# Cosmic.net
KiCad netlist of a schematic drawn in Altium Designer
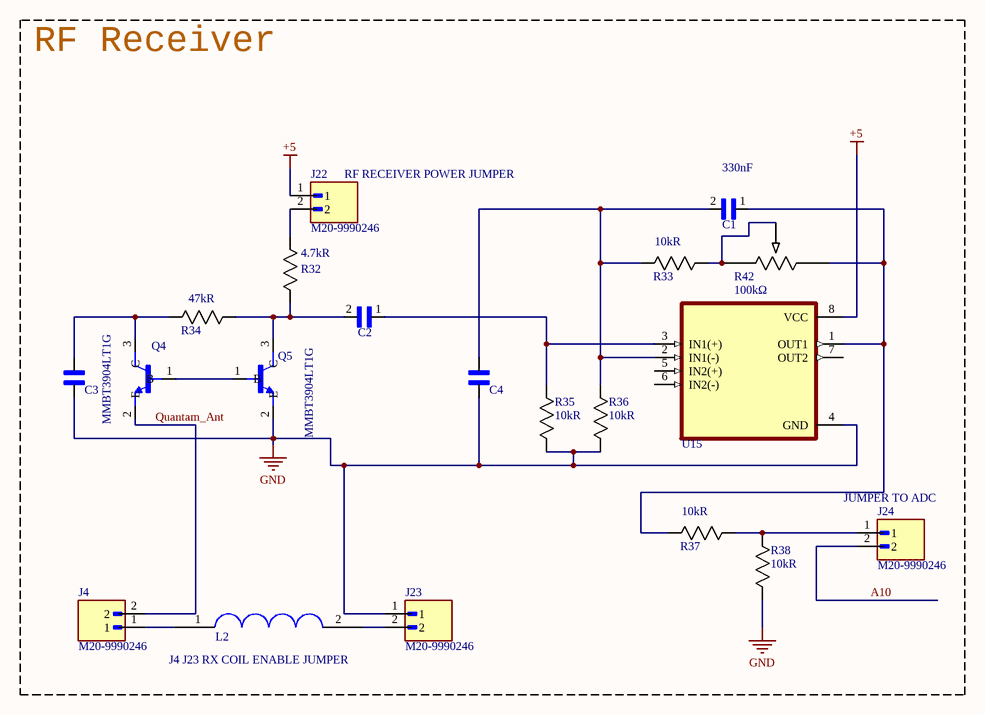
[diagram p0: Cosmic.SchDoc]

(export (version "E")
  (design (tool "Eeschema 10.0.6"))
  (components
    (comp (ref "C1")
      (value "GRM31C5C1E334GE01L")
      (footprint "CAP_1206")
      (description "Cap, 0.33Uf, 25V, 1206, C0G/Np0 Rohs Compliant: Yes ¦Murata GRM31C5C1E334GE01L")
      (fields
        (field (name "MANUFACTURER") "Murata")
        (field (name "CAPACITANCE") "330nF")
        (field (name "TOLERANCE") "2%")
      )
      (libsource (lib "Passive") (part "C334_1206"))
    )
    (comp (ref "C2")
      (value "GRM31C5C1E334GE01L")
      (footprint "CAP_1206")
      (description "Cap, 0.33Uf, 25V, 1206, C0G/Np0 Rohs Compliant: Yes ¦Murata GRM31C5C1E334GE01L")
      (fields (field (name "MANUFACTURER") "Murata") (field (name "TOLERANCE") "2%"))
      (libsource (lib "Passive") (part "C334_1206"))
    )
    (comp (ref "C3")
      (value "CL21A106KOQNNNG")
      (footprint "CAPC2012X140N")
      (description "10 ÂµF Â±10% 16V Ceramic Capacitor X5R 0805 (2012 Metric)")
      (fields (field (name "MF") "Samsung Electro-Mechanics"))
      (libsource (lib "Passive") (part "10uF16v0805"))
    )
    (comp (ref "C4")
      (value "CL21A106KOQNNNG")
      (footprint "CAPC2012X140N")
      (description "10 ÂµF Â±10% 16V Ceramic Capacitor X5R 0805 (2012 Metric)")
      (fields (field (name "MF") "Samsung Electro-Mechanics"))
      (libsource (lib "Passive") (part "10uF16v0805"))
    )
    (comp (ref "J4")
      (value "M20-9990246")
      (footprint "HARWIN_M20-9990246")
      (description "2.54mm (0.1) Pitch SIL Vertical Throughboard Pin Header, 6.1mm mating pin height, tin, 2 contacts")
      (fields (field (name "MF") "Harwin"))
      (libsource (lib "koncept") (part "M20-9990246"))
    )
    (comp (ref "J22")
      (value "M20-9990246")
      (footprint "HARWIN_M20-9990246")
      (description "2.54mm (0.1) Pitch SIL Vertical Throughboard Pin Header, 6.1mm mating pin height, tin, 2 contacts")
      (fields (field (name "MF") "Harwin"))
      (libsource (lib "") (part "M20-9990246_1"))
    )
    (comp (ref "J23")
      (value "M20-9990246")
      (footprint "HARWIN_M20-9990246")
      (description "2.54mm (0.1) Pitch SIL Vertical Throughboard Pin Header, 6.1mm mating pin height, tin, 2 contacts")
      (fields (field (name "MF") "Harwin"))
      (libsource (lib "") (part "M20-9990246_1"))
    )
    (comp (ref "J24")
      (value "M20-9990246")
      (footprint "HARWIN_M20-9990246")
      (description "2.54mm (0.1) Pitch SIL Vertical Throughboard Pin Header, 6.1mm mating pin height, tin, 2 contacts")
      (fields (field (name "MF") "Harwin"))
      (libsource (lib "") (part "M20-9990246_1"))
    )
    (comp (ref "L2")
      (value "COIL_PLANNER_A")
      (footprint "COIL_PLANNER_A")
      (libsource (lib "koncept") (part "COIL_PLANNER_A"))
    )
    (comp (ref "Q4")
      (value "MMBT3904LT1G")
      (footprint "SOT95P240X111-3N")
      (fields (field (name "MF") "ON Semiconductor"))
      (libsource (lib "") (part "MMBT3904LT1G_1"))
    )
    (comp (ref "Q5")
      (value "MMBT3904LT1G")
      (footprint "SOT95P240X111-3N")
      (fields (field (name "MF") "ON Semiconductor"))
      (libsource (lib "Passive") (part "MMBT3904LT1G"))
    )
    (comp (ref "R32")
      (value "RC1206FR-074K7L")
      (footprint "STA_RMCF1206_STP-L")
      (description "SMD Chip Resistor 4.7 Kohm ½ 1% 250 Mw 1206 [3216 Metric] Thick Film General Purpose")
      (fields
        (field (name "MANUFACTURER") "Yageo")
        (field (name "TOLERANCE") "1%")
        (field (name "RESISTANCE") "4.7kR")
      )
      (libsource (lib "Passive") (part "R4K7_1206F"))
    )
    (comp (ref "R33")
      (value "RC1206FR-0710KL")
      (footprint "STA_RMCF1206_STP-L")
      (description "250Mw Thick Film Resistors 100Ppm/ 1% 10K 1206 Chip Resistor Surface Mount Rohs")
      (fields
        (field (name "MANUFACTURER") "Yageo")
        (field (name "RESISTANCE") "10kR")
        (field (name "TOLERANCE") "1%")
      )
      (libsource (lib "Passive") (part "R10K-1206"))
    )
    (comp (ref "R34")
      (value "CRGCQ1206F47K")
      (footprint "STA_RMCF1206_STP-L")
      (description "SMD Chip Resistor, 47 kOhm, ± 1%, 250 mW, 1206 [3216 Metric], Thick Film, General Purpose")
      (fields
        (field (name "MANUFACTURER") "TE Connectivity")
        (field (name "RESISTANCE") "47kR")
        (field (name "TOLERANCE") "1%")
      )
      (libsource (lib "Passive") (part "R47K1206F"))
    )
    (comp (ref "R35")
      (value "RC1206FR-0710KL")
      (footprint "STA_RMCF1206_STP-L")
      (description "250Mw Thick Film Resistors 100Ppm/ 1% 10K 1206 Chip Resistor Surface Mount Rohs")
      (fields
        (field (name "MANUFACTURER") "Yageo")
        (field (name "RESISTANCE") "10kR")
        (field (name "TOLERANCE") "1%")
      )
      (libsource (lib "Passive") (part "R10K-1206"))
    )
    (comp (ref "R36")
      (value "RC1206FR-0710KL")
      (footprint "STA_RMCF1206_STP-L")
      (description "250Mw Thick Film Resistors 100Ppm/ 1% 10K 1206 Chip Resistor Surface Mount Rohs")
      (fields
        (field (name "MANUFACTURER") "Yageo")
        (field (name "RESISTANCE") "10kR")
        (field (name "TOLERANCE") "1%")
      )
      (libsource (lib "Passive") (part "R10K-1206"))
    )
    (comp (ref "R37")
      (value "RC1206FR-0710KL")
      (footprint "STA_RMCF1206_STP-L")
      (description "250Mw Thick Film Resistors 100Ppm/ 1% 10K 1206 Chip Resistor Surface Mount Rohs")
      (fields
        (field (name "MANUFACTURER") "Yageo")
        (field (name "RESISTANCE") "10kR")
        (field (name "TOLERANCE") "1%")
      )
      (libsource (lib "Passive") (part "R10K-1206"))
    )
    (comp (ref "R38")
      (value "RC1206FR-0710KL")
      (footprint "STA_RMCF1206_STP-L")
      (description "250Mw Thick Film Resistors 100Ppm/ 1% 10K 1206 Chip Resistor Surface Mount Rohs")
      (fields
        (field (name "MANUFACTURER") "Yageo")
        (field (name "RESISTANCE") "10kR")
        (field (name "TOLERANCE") "1%")
      )
      (libsource (lib "Passive") (part "R10K-1206"))
    )
    (comp (ref "R42")
      (value "PV36W104C01B00")
      (footprint "POT_PV36W_BRN")
      (description "Cermet trimmer potentiometer, 25 turns, 100 kΩ, 0.5 W, THT, on top, PV36W104C01B00")
      (fields
        (field (name "MANUFACTURER") "Bourns")
        (field (name "TOLERANCE") "10%")
        (field (name "RESISTANCE") "100kΩ")
      )
      (libsource (lib "Passive") (part "POT100K"))
    )
    (comp (ref "U15")
      (value "LM358MX/NOPB")
      (footprint "SOIC127P599X175-8N")
      (description "ROHS3Compliant EAR99 LM358 Tape & Reel (TR) op amp amplifier circuit 4.9mm 0.05muA 7mV 1000kHz")
      (fields (field (name "MANUFACTURER") "TI National Semiconductor"))
      (libsource (lib "koncept") (part "LM358MX/NOPB"))
    )
  )
  (nets
    (net (code "1") (name "+5") (class "Default")
      (node (ref "J22") (pin "1") (pinfunction "1_1") (pintype "passive"))
      (node (ref "U15") (pin "8") (pinfunction "VCC_8") (pintype "power_in"))
    )
    (net (code "2") (name "/A10") (class "Default")
      (node (ref "J24") (pin "2") (pinfunction "2_2") (pintype "passive"))
    )
    (net (code "3") (name "/Quantam_Ant") (class "Default")
      (node (ref "J4") (pin "2") (pinfunction "2_2") (pintype "passive"))
      (node (ref "Q4") (pin "2") (pinfunction "E_2") (pintype "passive"))
    )
    (net (code "4") (name "GND") (class "Default")
      (node (ref "C3") (pin "1") (pinfunction "1_1") (pintype "passive"))
      (node (ref "C4") (pin "1") (pinfunction "1_1") (pintype "passive"))
      (node (ref "J23") (pin "1") (pinfunction "1_1") (pintype "passive"))
      (node (ref "Q5") (pin "2") (pinfunction "E_2") (pintype "passive"))
      (node (ref "R35") (pin "1") (pinfunction "1_1") (pintype "passive"))
      (node (ref "R36") (pin "1") (pinfunction "1_1") (pintype "passive"))
      (node (ref "R38") (pin "1") (pinfunction "1_1") (pintype "passive"))
      (node (ref "U15") (pin "4") (pinfunction "GND_4") (pintype "power_in"))
    )
    (net (code "5") (name "Net-(J4-Pad1)") (class "Default")
      (node (ref "J4") (pin "1") (pinfunction "1_1") (pintype "passive"))
      (node (ref "L2") (pin "1") (pinfunction "1_1") (pintype "passive"))
    )
    (net (code "6") (name "Net-(J22-Pad2)") (class "Default")
      (node (ref "J22") (pin "2") (pinfunction "2_2") (pintype "passive"))
      (node (ref "R32") (pin "2") (pinfunction "2_2") (pintype "passive"))
    )
    (net (code "7") (name "Net-(J23-Pad2)") (class "Default")
      (node (ref "J23") (pin "2") (pinfunction "2_2") (pintype "passive"))
      (node (ref "L2") (pin "2") (pinfunction "2_2") (pintype "passive"))
    )
    (net (code "8") (name "Net-(J24-Pad1)") (class "Default")
      (node (ref "J24") (pin "1") (pinfunction "1_1") (pintype "passive"))
      (node (ref "R37") (pin "2") (pinfunction "2_2") (pintype "passive"))
      (node (ref "R38") (pin "2") (pinfunction "2_2") (pintype "passive"))
    )
    (net (code "9") (name "Net-(Q4-B)") (class "Default")
      (node (ref "Q4") (pin "1") (pinfunction "B_1") (pintype "passive"))
      (node (ref "Q5") (pin "1") (pinfunction "B_1") (pintype "passive"))
    )
    (net (code "10") (name "Net-(Q4-C)") (class "Default")
      (node (ref "C3") (pin "2") (pinfunction "2_2") (pintype "passive"))
      (node (ref "Q4") (pin "3") (pinfunction "C_3") (pintype "passive"))
      (node (ref "R34") (pin "1") (pinfunction "1_1") (pintype "passive"))
    )
    (net (code "11") (name "Net-(Q5-C)") (class "Default")
      (node (ref "C2") (pin "2") (pinfunction "2_2") (pintype "passive"))
      (node (ref "Q5") (pin "3") (pinfunction "C_3") (pintype "passive"))
      (node (ref "R32") (pin "1") (pinfunction "1_1") (pintype "passive"))
      (node (ref "R34") (pin "2") (pinfunction "2_2") (pintype "passive"))
    )
    (net (code "12") (name "Net-(R33-Pad2)") (class "Default")
      (node (ref "R33") (pin "2") (pinfunction "2_2") (pintype "passive"))
      (node (ref "R42") (pin "1") (pinfunction "1_1") (pintype "passive"))
      (node (ref "R42") (pin "2") (pinfunction "2_2") (pintype "passive"))
    )
    (net (code "13") (name "Net-(U15-IN1(+))") (class "Default")
      (node (ref "C2") (pin "1") (pinfunction "1_1") (pintype "passive"))
      (node (ref "R35") (pin "2") (pinfunction "2_2") (pintype "passive"))
      (node (ref "U15") (pin "3") (pinfunction "IN1(+)_3") (pintype "input"))
    )
    (net (code "14") (name "Net-(U15-IN1(-))") (class "Default")
      (node (ref "C1") (pin "2") (pinfunction "2_2") (pintype "passive"))
      (node (ref "C4") (pin "2") (pinfunction "2_2") (pintype "passive"))
      (node (ref "R33") (pin "1") (pinfunction "1_1") (pintype "passive"))
      (node (ref "R36") (pin "2") (pinfunction "2_2") (pintype "passive"))
      (node (ref "U15") (pin "2") (pinfunction "IN1(-)_2") (pintype "input"))
    )
    (net (code "15") (name "Net-(U15-OUT1)") (class "Default")
      (node (ref "C1") (pin "1") (pinfunction "1_1") (pintype "passive"))
      (node (ref "R37") (pin "1") (pinfunction "1_1") (pintype "passive"))
      (node (ref "R42") (pin "3") (pinfunction "3_3") (pintype "passive"))
      (node (ref "U15") (pin "1") (pinfunction "OUT1_1") (pintype "output"))
    )
    (net (code "16") (name "unconnected-(U15-IN2(+)-Pad5)") (class "Default")
      (node (ref "U15") (pin "5") (pinfunction "IN2(+)_5") (pintype "input"))
    )
    (net (code "17") (name "unconnected-(U15-IN2(-)-Pad6)") (class "Default")
      (node (ref "U15") (pin "6") (pinfunction "IN2(-)_6") (pintype "input"))
    )
    (net (code "18") (name "unconnected-(U15-OUT2-Pad7)") (class "Default")
      (node (ref "U15") (pin "7") (pinfunction "OUT2_7") (pintype "output"))
    )
  )
)
